# eMMC.net
KiCad netlist of a schematic drawn in Altium Designer
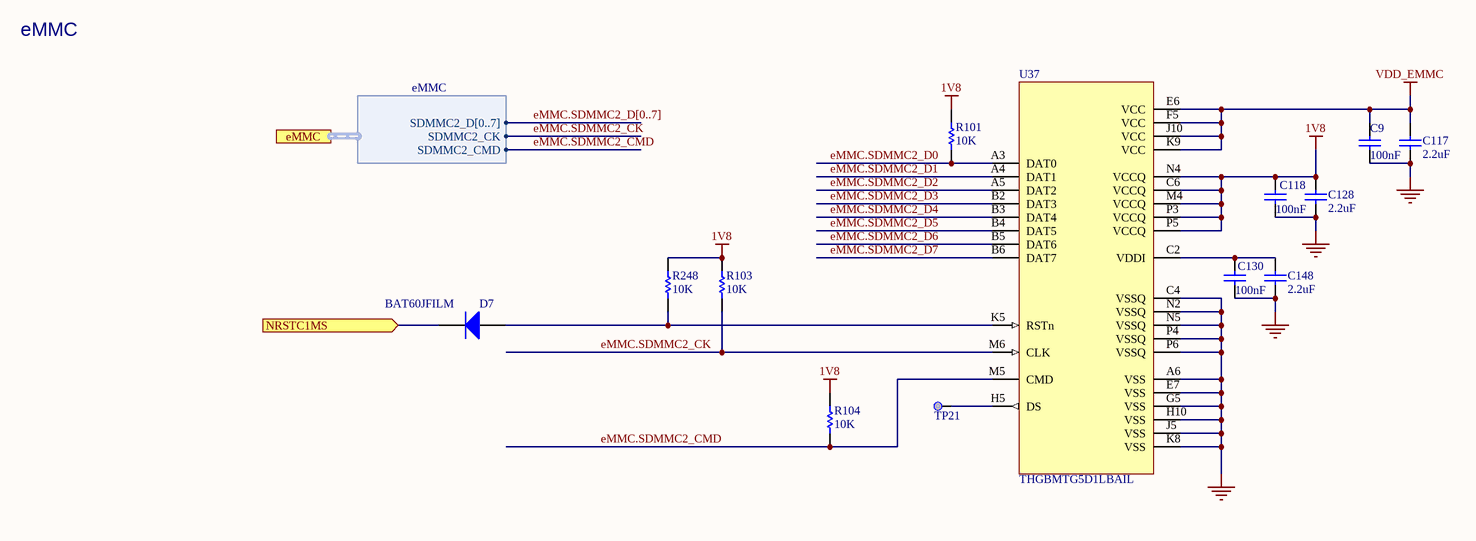
[diagram p0: eMMC.SchDoc]

(export (version "E")
  (design (tool "Eeschema 10.0.6"))
  (components
    (comp (ref "C9")
      (value "100nF")
      (footprint "C0402")
      (description "Capacitor, MLCC, 100nF, 16V, X7R, +/-10%, 0402, T=0.5mm")
      (fields (field (name "INTERNAL_PART_NUMBER") "MCD-00006") (field (name "MANUFACTURER") "YAGEO"))
      (libsource (lib "MCD_PARTS_database") (part "Capacitor"))
    )
    (comp (ref "C117")
      (value "2.2uF")
      (footprint "C0402")
      (description "Capacitor, MLCC, 2.2uF, 6.3V, X5R, +/-10%, 0402, T=0.5mm")
      (fields (field (name "INTERNAL_PART_NUMBER") "MCD-02606") (field (name "MANUFACTURER") "YAGEO"))
      (libsource (lib "MCD_PARTS_database") (part "Capacitor"))
    )
    (comp (ref "C118")
      (value "100nF")
      (footprint "C0402")
      (description "Capacitor, MLCC, 100nF, 16V, X7R, +/-10%, 0402, T=0.5mm")
      (fields (field (name "INTERNAL_PART_NUMBER") "MCD-00006") (field (name "MANUFACTURER") "YAGEO"))
      (libsource (lib "MCD_PARTS_database") (part "Capacitor"))
    )
    (comp (ref "C128")
      (value "2.2uF")
      (footprint "C0402")
      (description "Capacitor, MLCC, 2.2uF, 6.3V, X5R, +/-10%, 0402, T=0.5mm")
      (fields (field (name "INTERNAL_PART_NUMBER") "MCD-02606") (field (name "MANUFACTURER") "YAGEO"))
      (libsource (lib "MCD_PARTS_database") (part "Capacitor"))
    )
    (comp (ref "C130")
      (value "100nF")
      (footprint "C0402")
      (description "Capacitor, MLCC, 100nF, 16V, X7R, +/-10%, 0402, T=0.5mm")
      (fields (field (name "INTERNAL_PART_NUMBER") "MCD-00006") (field (name "MANUFACTURER") "YAGEO"))
      (libsource (lib "MCD_PARTS_database") (part "Capacitor"))
    )
    (comp (ref "C148")
      (value "2.2uF")
      (footprint "C0402")
      (description "Capacitor, MLCC, 2.2uF, 6.3V, X5R, +/-10%, 0402, T=0.5mm")
      (fields (field (name "INTERNAL_PART_NUMBER") "MCD-02606") (field (name "MANUFACTURER") "YAGEO"))
      (libsource (lib "MCD_PARTS_database") (part "Capacitor"))
    )
    (comp (ref "D7")
      (value "BAT60JFILM")
      (footprint "DIO_SOD323")
      (fields
        (field (name "INTERNAL_PART_NUMBER") "MCD-00034")
        (field (name "BMS_PART_NUMBER") "9151097")
        (field (name "MANUFACTURER") "STMICROELECTRONICS")
      )
      (libsource (lib "MCD_PARTS_database") (part "BAT60JFILM"))
    )
    (comp (ref "R101")
      (value "10K")
      (footprint "R0402")
      (description "Resistor,10K,0402,1%,1/16W")
      (fields
        (field (name "INTERNAL_PART_NUMBER") "MCD-00053")
        (field (name "MANUFACTURER_PART_NUMBER") "RC0402FR-0710KL")
        (field (name "PROVIDED_BY") "SUBCO")
      )
      (libsource (lib "MCD_PARTS_database") (part "Resistor"))
    )
    (comp (ref "R103")
      (value "10K")
      (footprint "R0402")
      (description "Resistor,10K,0402,1%,1/16W")
      (fields
        (field (name "INTERNAL_PART_NUMBER") "MCD-00053")
        (field (name "MANUFACTURER_PART_NUMBER") "RC0402FR-0710KL")
        (field (name "PROVIDED_BY") "SUBCO")
      )
      (libsource (lib "MCD_PARTS_database") (part "Resistor"))
    )
    (comp (ref "R104")
      (value "10K")
      (footprint "R0402")
      (description "Resistor,10K,0402,1%,1/16W")
      (fields
        (field (name "INTERNAL_PART_NUMBER") "MCD-00053")
        (field (name "MANUFACTURER_PART_NUMBER") "RC0402FR-0710KL")
        (field (name "PROVIDED_BY") "SUBCO")
      )
      (libsource (lib "MCD_PARTS_database") (part "Resistor"))
    )
    (comp (ref "R248")
      (value "10K")
      (footprint "R0402")
      (description "Resistor,10K,0402,1%,1/16W")
      (fields
        (field (name "INTERNAL_PART_NUMBER") "MCD-00053")
        (field (name "MANUFACTURER_PART_NUMBER") "RC0402FR-0710KL")
        (field (name "PROVIDED_BY") "SUBCO")
      )
      (libsource (lib "MCD_PARTS_database") (part "Resistor"))
    )
    (comp (ref "TP21")
      (value "Test Point")
      (footprint "TP_SMD_1MM")
      (description "Test Point 1mm")
      (fields
        (field (name "INTERNAL_PART_NUMBER") "MCD-00074")
        (field (name "MANUFACTURER_PART_NUMBER") "n/a")
      )
      (libsource (lib "MCD_PARTS_database") (part "Test Point"))
    )
    (comp (ref "U37")
      (value "THGBMTG5D1LBAIL")
      (footprint "ICC_P-WFBGA153_13X11P5_P050")
      (description "Memory, eMMC, 4GB, 15nm ,WFBGA , 153 pins")
      (fields (field (name "INTERNAL_PART_NUMBER") "MCD-02799") (field (name "MANUFACTURER") "KIOXIA"))
      (libsource (lib "MCD_PARTS_database") (part "eMMC_THGBMTG5D1LBAIL"))
    )
  )
  (nets
    (net (code "2") (name "/NRSTC1MS") (class "Default")
      (node (ref "D7") (pin "2") (pinfunction "K_2") (pintype "passive"))
    )
    (net (code "3") (name "/eMMC.SDMMC2_CK") (class "Default")
      (node (ref "R103") (pin "1") (pinfunction "1_1") (pintype "passive"))
      (node (ref "U37") (pin "M6") (pinfunction "CLK_M6") (pintype "input"))
    )
    (net (code "4") (name "/eMMC.SDMMC2_CMD") (class "Default")
      (node (ref "R104") (pin "1") (pinfunction "1_1") (pintype "passive"))
      (node (ref "U37") (pin "M5") (pinfunction "CMD_M5") (pintype "passive"))
    )
    (net (code "5") (name "/eMMC.SDMMC2_D0") (class "Default")
      (node (ref "R101") (pin "1") (pinfunction "1_1") (pintype "passive"))
      (node (ref "U37") (pin "A3") (pinfunction "DAT0_A3") (pintype "passive"))
    )
    (net (code "6") (name "/eMMC.SDMMC2_D1") (class "Default")
      (node (ref "U37") (pin "A4") (pinfunction "DAT1_A4") (pintype "passive"))
    )
    (net (code "7") (name "/eMMC.SDMMC2_D2") (class "Default")
      (node (ref "U37") (pin "A5") (pinfunction "DAT2_A5") (pintype "passive"))
    )
    (net (code "8") (name "/eMMC.SDMMC2_D3") (class "Default")
      (node (ref "U37") (pin "B2") (pinfunction "DAT3_B2") (pintype "passive"))
    )
    (net (code "9") (name "/eMMC.SDMMC2_D4") (class "Default")
      (node (ref "U37") (pin "B3") (pinfunction "DAT4_B3") (pintype "passive"))
    )
    (net (code "10") (name "/eMMC.SDMMC2_D5") (class "Default")
      (node (ref "U37") (pin "B4") (pinfunction "DAT5_B4") (pintype "passive"))
    )
    (net (code "11") (name "/eMMC.SDMMC2_D6") (class "Default")
      (node (ref "U37") (pin "B5") (pinfunction "DAT6_B5") (pintype "passive"))
    )
    (net (code "12") (name "/eMMC.SDMMC2_D7") (class "Default")
      (node (ref "U37") (pin "B6") (pinfunction "DAT7_B6") (pintype "passive"))
    )
    (net (code "15") (name "1V8") (class "Default")
      (node (ref "C118") (pin "2") (pinfunction "2_2") (pintype "passive"))
      (node (ref "C128") (pin "2") (pinfunction "2_2") (pintype "passive"))
      (node (ref "R101") (pin "2") (pinfunction "2_2") (pintype "passive"))
      (node (ref "R103") (pin "2") (pinfunction "2_2") (pintype "passive"))
      (node (ref "R104") (pin "2") (pinfunction "2_2") (pintype "passive"))
      (node (ref "R248") (pin "2") (pinfunction "2_2") (pintype "passive"))
      (node (ref "U37") (pin "C6") (pinfunction "VCCQ_C6") (pintype "passive"))
      (node (ref "U37") (pin "M4") (pinfunction "VCCQ_M4") (pintype "passive"))
      (node (ref "U37") (pin "N4") (pinfunction "VCCQ_N4") (pintype "passive"))
      (node (ref "U37") (pin "P3") (pinfunction "VCCQ_P3") (pintype "passive"))
      (node (ref "U37") (pin "P5") (pinfunction "VCCQ_P5") (pintype "passive"))
    )
    (net (code "16") (name "GND") (class "Default")
      (node (ref "C117") (pin "1") (pinfunction "1_1") (pintype "passive"))
      (node (ref "C118") (pin "1") (pinfunction "1_1") (pintype "passive"))
      (node (ref "C128") (pin "1") (pinfunction "1_1") (pintype "passive"))
      (node (ref "C130") (pin "1") (pinfunction "1_1") (pintype "passive"))
      (node (ref "C148") (pin "1") (pinfunction "1_1") (pintype "passive"))
      (node (ref "C9") (pin "1") (pinfunction "1_1") (pintype "passive"))
      (node (ref "U37") (pin "A6") (pinfunction "VSS_A6") (pintype "passive"))
      (node (ref "U37") (pin "C4") (pinfunction "VSSQ_C4") (pintype "passive"))
      (node (ref "U37") (pin "E7") (pinfunction "VSS_E7") (pintype "passive"))
      (node (ref "U37") (pin "G5") (pinfunction "VSS_G5") (pintype "passive"))
      (node (ref "U37") (pin "H10") (pinfunction "VSS_H10") (pintype "passive"))
      (node (ref "U37") (pin "J5") (pinfunction "VSS_J5") (pintype "passive"))
      (node (ref "U37") (pin "K8") (pinfunction "VSS_K8") (pintype "passive"))
      (node (ref "U37") (pin "N2") (pinfunction "VSSQ_N2") (pintype "passive"))
      (node (ref "U37") (pin "N5") (pinfunction "VSSQ_N5") (pintype "passive"))
      (node (ref "U37") (pin "P4") (pinfunction "VSSQ_P4") (pintype "passive"))
      (node (ref "U37") (pin "P6") (pinfunction "VSSQ_P6") (pintype "passive"))
    )
    (net (code "17") (name "Net-(D7-A)") (class "Default")
      (node (ref "D7") (pin "1") (pinfunction "A_1") (pintype "passive"))
      (node (ref "R248") (pin "1") (pinfunction "1_1") (pintype "passive"))
      (node (ref "U37") (pin "K5") (pinfunction "RSTn_K5") (pintype "input"))
    )
    (net (code "18") (name "Net-(U37-DS)") (class "Default")
      (node (ref "TP21") (pin "1") (pinfunction "1_1") (pintype "passive"))
      (node (ref "U37") (pin "H5") (pinfunction "DS_H5") (pintype "output"))
    )
    (net (code "19") (name "Net-(U37-VDDI)") (class "Default")
      (node (ref "C130") (pin "2") (pinfunction "2_2") (pintype "passive"))
      (node (ref "C148") (pin "2") (pinfunction "2_2") (pintype "passive"))
      (node (ref "U37") (pin "C2") (pinfunction "VDDI_C2") (pintype "passive"))
    )
    (net (code "20") (name "VDD_EMMC") (class "Default")
      (node (ref "C117") (pin "2") (pinfunction "2_2") (pintype "passive"))
      (node (ref "C9") (pin "2") (pinfunction "2_2") (pintype "passive"))
      (node (ref "U37") (pin "E6") (pinfunction "VCC_E6") (pintype "passive"))
      (node (ref "U37") (pin "F5") (pinfunction "VCC_F5") (pintype "passive"))
      (node (ref "U37") (pin "J10") (pinfunction "VCC_J10") (pintype "passive"))
      (node (ref "U37") (pin "K9") (pinfunction "VCC_K9") (pintype "passive"))
    )
  )
)
